# schematic.net
KiCad netlist of a schematic drawn in EAGLE
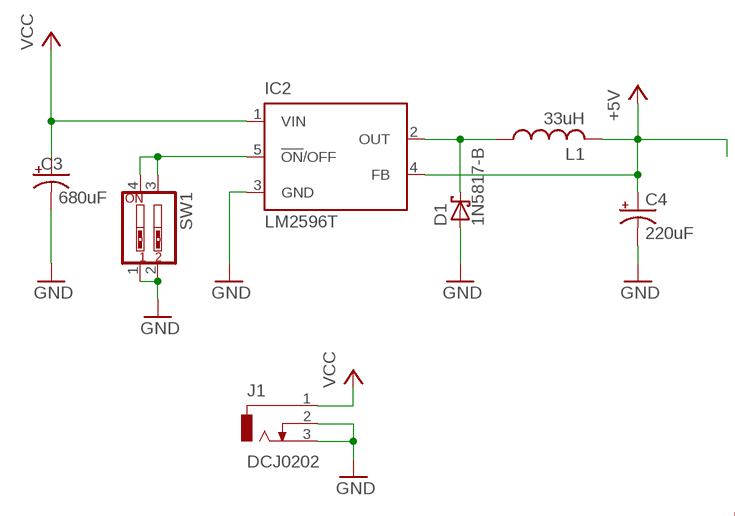
[diagram p0: schematic, sheet 1, part 1 of 2]
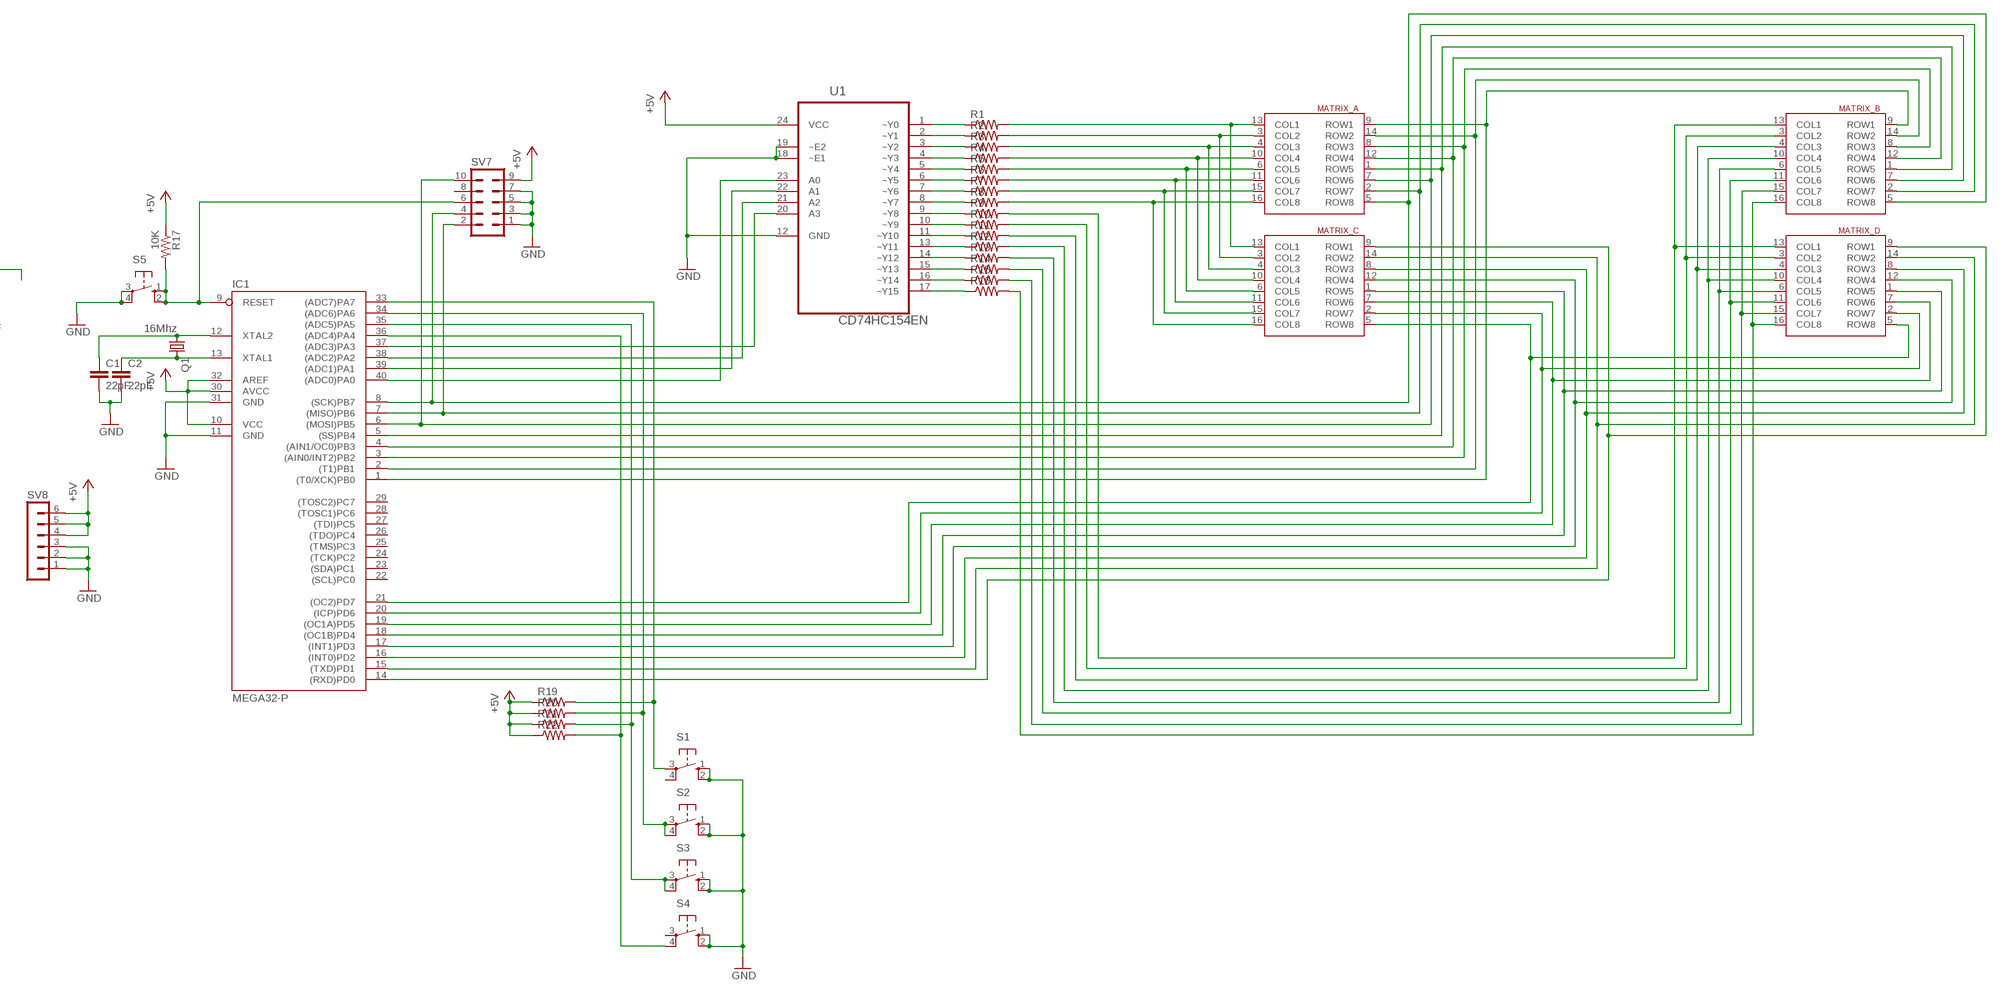
[diagram p1: schematic, sheet 1, part 2 of 2]

(export (version "E")
  (design (tool "Eeschema 10.0.6"))
  (components
    (comp (ref "C1")
      (value "22pF")
      (footprint "eagle-import:C025-024X044")
      (libsource (lib "eagle-import") (part "C-EU025-024X044"))
    )
    (comp (ref "C2")
      (value "22pF")
      (footprint "eagle-import:C025-024X044")
      (libsource (lib "eagle-import") (part "C-EU025-024X044"))
    )
    (comp (ref "C3")
      (value "680uF")
      (footprint "eagle-import:E3,5-8")
      (libsource (lib "eagle-import") (part "CPOL-USE3.5-8"))
    )
    (comp (ref "C4")
      (value "220uF")
      (footprint "eagle-import:E3,5-8")
      (libsource (lib "eagle-import") (part "CPOL-USE3.5-8"))
    )
    (comp (ref "D1")
      (value "1N5817-B")
      (footprint "eagle-import:DO41-7.6")
      (libsource (lib "eagle-import") (part "1N5817-B"))
    )
    (comp (ref "IC1")
      (value "MEGA32-P")
      (footprint "eagle-import:DIL40")
      (fields (field (name "MPN") "ATMEGA32-16PU"))
      (libsource (lib "eagle-import") (part "MEGA32-P"))
    )
    (comp (ref "IC2")
      (value "LM2596T")
      (footprint "eagle-import:T05D")
      (fields (field (name "MPN") "LM2596T-ADJ/LF02"))
      (libsource (lib "eagle-import") (part "LM2596T"))
    )
    (comp (ref "J1")
      (value "DCJ0202")
      (footprint "eagle-import:DCJ0202")
      (libsource (lib "eagle-import") (part "DCJ0202"))
    )
    (comp (ref "L1")
      (value "33uH")
      (footprint "eagle-import:0207_10")
      (libsource (lib "eagle-import") (part "L-US0207/10"))
    )
    (comp (ref "MATRIX_A")
      (value "LED_8X8_MATRIXYGD2/A")
      (footprint "eagle-import:MATRIX_8X8_38MM")
      (libsource (lib "eagle-import") (part "LED_8X8_MATRIXYGD2/A"))
    )
    (comp (ref "MATRIX_B")
      (value "LED_8X8_MATRIXYGD2/A")
      (footprint "eagle-import:MATRIX_8X8_38MM")
      (libsource (lib "eagle-import") (part "LED_8X8_MATRIXYGD2/A"))
    )
    (comp (ref "MATRIX_C")
      (value "LED_8X8_MATRIXYGD2/A")
      (footprint "eagle-import:MATRIX_8X8_38MM")
      (libsource (lib "eagle-import") (part "LED_8X8_MATRIXYGD2/A"))
    )
    (comp (ref "MATRIX_D")
      (value "LED_8X8_MATRIXYGD2/A")
      (footprint "eagle-import:MATRIX_8X8_38MM")
      (libsource (lib "eagle-import") (part "LED_8X8_MATRIXYGD2/A"))
    )
    (comp (ref "Q1")
      (value "16Mhz")
      (footprint "eagle-import:HC49_S")
      (libsource (lib "eagle-import") (part "CRYSTALHC49S"))
    )
    (comp (ref "R1")
      (value "R-US_0204/2V")
      (footprint "eagle-import:0204V")
      (libsource (lib "eagle-import") (part "R-US_0204/2V"))
    )
    (comp (ref "R2")
      (value "R-US_0204/2V")
      (footprint "eagle-import:0204V")
      (libsource (lib "eagle-import") (part "R-US_0204/2V"))
    )
    (comp (ref "R3")
      (value "R-US_0204/2V")
      (footprint "eagle-import:0204V")
      (libsource (lib "eagle-import") (part "R-US_0204/2V"))
    )
    (comp (ref "R4")
      (value "R-US_0204/2V")
      (footprint "eagle-import:0204V")
      (libsource (lib "eagle-import") (part "R-US_0204/2V"))
    )
    (comp (ref "R5")
      (value "R-US_0204/2V")
      (footprint "eagle-import:0204V")
      (libsource (lib "eagle-import") (part "R-US_0204/2V"))
    )
    (comp (ref "R6")
      (value "R-US_0204/2V")
      (footprint "eagle-import:0204V")
      (libsource (lib "eagle-import") (part "R-US_0204/2V"))
    )
    (comp (ref "R7")
      (value "R-US_0204/2V")
      (footprint "eagle-import:0204V")
      (libsource (lib "eagle-import") (part "R-US_0204/2V"))
    )
    (comp (ref "R8")
      (value "R-US_0204/2V")
      (footprint "eagle-import:0204V")
      (libsource (lib "eagle-import") (part "R-US_0204/2V"))
    )
    (comp (ref "R9")
      (value "R-US_0204/2V")
      (footprint "eagle-import:0204V")
      (libsource (lib "eagle-import") (part "R-US_0204/2V"))
    )
    (comp (ref "R10")
      (value "R-US_0204/2V")
      (footprint "eagle-import:0204V")
      (libsource (lib "eagle-import") (part "R-US_0204/2V"))
    )
    (comp (ref "R11")
      (value "R-US_0204/2V")
      (footprint "eagle-import:0204V")
      (libsource (lib "eagle-import") (part "R-US_0204/2V"))
    )
    (comp (ref "R12")
      (value "R-US_0204/2V")
      (footprint "eagle-import:0204V")
      (libsource (lib "eagle-import") (part "R-US_0204/2V"))
    )
    (comp (ref "R13")
      (value "R-US_0204/2V")
      (footprint "eagle-import:0204V")
      (libsource (lib "eagle-import") (part "R-US_0204/2V"))
    )
    (comp (ref "R14")
      (value "R-US_0204/2V")
      (footprint "eagle-import:0204V")
      (libsource (lib "eagle-import") (part "R-US_0204/2V"))
    )
    (comp (ref "R15")
      (value "R-US_0204/2V")
      (footprint "eagle-import:0204V")
      (libsource (lib "eagle-import") (part "R-US_0204/2V"))
    )
    (comp (ref "R16")
      (value "R-US_0204/2V")
      (footprint "eagle-import:0204V")
      (libsource (lib "eagle-import") (part "R-US_0204/2V"))
    )
    (comp (ref "R17")
      (value "10K")
      (footprint "eagle-import:0204_7")
      (libsource (lib "eagle-import") (part "resistor_348_R-US_0204/7"))
    )
    (comp (ref "R19")
      (value "R-US_0204/7")
      (footprint "eagle-import:0204_7")
      (libsource (lib "eagle-import") (part "R-US_0204/7"))
    )
    (comp (ref "R20")
      (value "R-US_0204/7")
      (footprint "eagle-import:0204_7")
      (libsource (lib "eagle-import") (part "R-US_0204/7"))
    )
    (comp (ref "R21")
      (value "R-US_0204/7")
      (footprint "eagle-import:0204_7")
      (libsource (lib "eagle-import") (part "R-US_0204/7"))
    )
    (comp (ref "R22")
      (value "R-US_0204/7")
      (footprint "eagle-import:0204_7")
      (libsource (lib "eagle-import") (part "R-US_0204/7"))
    )
    (comp (ref "S1")
      (value "10-XX")
      (footprint "eagle-import:B3F-10XX")
      (fields (field (name "MPN") "B3F-1000"))
      (libsource (lib "eagle-import") (part "10-XX"))
    )
    (comp (ref "S2")
      (value "10-XX")
      (footprint "eagle-import:B3F-10XX")
      (fields (field (name "MPN") "B3F-1000"))
      (libsource (lib "eagle-import") (part "10-XX"))
    )
    (comp (ref "S3")
      (value "10-XX")
      (footprint "eagle-import:B3F-10XX")
      (fields (field (name "MPN") "B3F-1000"))
      (libsource (lib "eagle-import") (part "10-XX"))
    )
    (comp (ref "S4")
      (value "10-XX")
      (footprint "eagle-import:B3F-10XX")
      (fields (field (name "MPN") "B3F-1000"))
      (libsource (lib "eagle-import") (part "10-XX"))
    )
    (comp (ref "S5")
      (value "10-XX")
      (footprint "eagle-import:B3F-10XX")
      (fields (field (name "MPN") "B3F-1000"))
      (libsource (lib "eagle-import") (part "10-XX"))
    )
    (comp (ref "SV7")
      (value "MA05-2")
      (footprint "eagle-import:MA05-2")
      (libsource (lib "eagle-import") (part "MA05-2"))
    )
    (comp (ref "SV8")
      (value "MA06-1")
      (footprint "eagle-import:MA06-1")
      (libsource (lib "eagle-import") (part "MA06-1"))
    )
    (comp (ref "SW1")
      (value "SW_DIP-2")
      (footprint "eagle-import:EDG-02")
      (libsource (lib "eagle-import") (part "SW_DIP-2"))
    )
    (comp (ref "U1")
      (value "CD74HC154EN")
      (footprint "eagle-import:DIP254P762X508-24")
      (libsource (lib "eagle-import") (part "CD74HC154EN"))
    )
  )
  (nets
    (net (code "1") (name "+5V") (class "Default")
      (node (ref "C4") (pin "+") (pinfunction "+_+") (pintype "passive"))
      (node (ref "IC1") (pin "10") (pinfunction "VCC_10") (pintype "power_in"))
      (node (ref "IC1") (pin "30") (pinfunction "AVCC_30") (pintype "power_in"))
      (node (ref "IC1") (pin "32") (pinfunction "AREF_32") (pintype "passive"))
      (node (ref "IC2") (pin "4") (pinfunction "FB_4") (pintype "input"))
      (node (ref "L1") (pin "2") (pinfunction "2_2") (pintype "passive"))
      (node (ref "R17") (pin "1") (pinfunction "1_1") (pintype "passive"))
      (node (ref "R19") (pin "1") (pinfunction "1_1") (pintype "passive"))
      (node (ref "R20") (pin "1") (pinfunction "1_1") (pintype "passive"))
      (node (ref "R21") (pin "1") (pinfunction "1_1") (pintype "passive"))
      (node (ref "R22") (pin "1") (pinfunction "1_1") (pintype "passive"))
      (node (ref "SV7") (pin "9") (pinfunction "9_9") (pintype "passive"))
      (node (ref "SV8") (pin "4") (pinfunction "4_4") (pintype "passive"))
      (node (ref "SV8") (pin "5") (pinfunction "5_5") (pintype "passive"))
      (node (ref "SV8") (pin "6") (pinfunction "6_6") (pintype "passive"))
      (node (ref "U1") (pin "24") (pinfunction "VCC_24") (pintype "power_in"))
    )
    (net (code "2") (name "GND") (class "Default")
      (node (ref "C1") (pin "2") (pinfunction "2_2") (pintype "passive"))
      (node (ref "C2") (pin "2") (pinfunction "2_2") (pintype "passive"))
      (node (ref "C3") (pin "-") (pinfunction "-_-") (pintype "passive"))
      (node (ref "C4") (pin "-") (pinfunction "-_-") (pintype "passive"))
      (node (ref "D1") (pin "A") (pinfunction "A_A") (pintype "passive"))
      (node (ref "IC1") (pin "11") (pinfunction "GND_11") (pintype "power_in"))
      (node (ref "IC1") (pin "31") (pinfunction "GND_31") (pintype "power_in"))
      (node (ref "IC2") (pin "3") (pinfunction "GND_3") (pintype "power_in"))
      (node (ref "J1") (pin "2") (pinfunction "2_2") (pintype "passive"))
      (node (ref "J1") (pin "3") (pinfunction "3_3") (pintype "passive"))
      (node (ref "S1") (pin "1") (pinfunction "S_1") (pintype "passive"))
      (node (ref "S1") (pin "2") (pinfunction "S1_2") (pintype "passive"))
      (node (ref "S2") (pin "1") (pinfunction "S_1") (pintype "passive"))
      (node (ref "S2") (pin "2") (pinfunction "S1_2") (pintype "passive"))
      (node (ref "S3") (pin "1") (pinfunction "S_1") (pintype "passive"))
      (node (ref "S3") (pin "2") (pinfunction "S1_2") (pintype "passive"))
      (node (ref "S4") (pin "1") (pinfunction "S_1") (pintype "passive"))
      (node (ref "S4") (pin "2") (pinfunction "S1_2") (pintype "passive"))
      (node (ref "S5") (pin "3") (pinfunction "P_3") (pintype "passive"))
      (node (ref "S5") (pin "4") (pinfunction "P1_4") (pintype "passive"))
      (node (ref "SV7") (pin "1") (pinfunction "1_1") (pintype "passive"))
      (node (ref "SV7") (pin "3") (pinfunction "3_3") (pintype "passive"))
      (node (ref "SV7") (pin "5") (pinfunction "5_5") (pintype "passive"))
      (node (ref "SV7") (pin "7") (pinfunction "7_7") (pintype "passive"))
      (node (ref "SV8") (pin "1") (pinfunction "1_1") (pintype "passive"))
      (node (ref "SV8") (pin "2") (pinfunction "2_2") (pintype "passive"))
      (node (ref "SV8") (pin "3") (pinfunction "3_3") (pintype "passive"))
      (node (ref "SW1") (pin "1") (pinfunction "1_1") (pintype "passive"))
      (node (ref "SW1") (pin "2") (pinfunction "2_2") (pintype "passive"))
      (node (ref "U1") (pin "12") (pinfunction "GND_12") (pintype "passive"))
      (node (ref "U1") (pin "18") (pinfunction "~{E1}_18") (pintype "input"))
      (node (ref "U1") (pin "19") (pinfunction "~{E2}_19") (pintype "input"))
    )
    (net (code "3") (name "Net-(IC1-(ADC0)PA0)") (class "Default")
      (node (ref "IC1") (pin "40") (pinfunction "(ADC0)PA0_40") (pintype "bidirectional"))
      (node (ref "U1") (pin "23") (pinfunction "A0_23") (pintype "input"))
    )
    (net (code "4") (name "Net-(IC1-(ADC1)PA1)") (class "Default")
      (node (ref "IC1") (pin "39") (pinfunction "(ADC1)PA1_39") (pintype "bidirectional"))
      (node (ref "U1") (pin "22") (pinfunction "A1_22") (pintype "input"))
    )
    (net (code "5") (name "Net-(IC1-(ADC2)PA2)") (class "Default")
      (node (ref "IC1") (pin "38") (pinfunction "(ADC2)PA2_38") (pintype "bidirectional"))
      (node (ref "U1") (pin "21") (pinfunction "A2_21") (pintype "input"))
    )
    (net (code "6") (name "Net-(IC1-(ADC3)PA3)") (class "Default")
      (node (ref "IC1") (pin "37") (pinfunction "(ADC3)PA3_37") (pintype "bidirectional"))
      (node (ref "U1") (pin "20") (pinfunction "A3_20") (pintype "input"))
    )
    (net (code "7") (name "Net-(IC1-(ADC4)PA4)") (class "Default")
      (node (ref "IC1") (pin "36") (pinfunction "(ADC4)PA4_36") (pintype "bidirectional"))
      (node (ref "R22") (pin "2") (pinfunction "2_2") (pintype "passive"))
      (node (ref "S4") (pin "4") (pinfunction "P1_4") (pintype "passive"))
    )
    (net (code "8") (name "Net-(IC1-(ADC5)PA5)") (class "Default")
      (node (ref "IC1") (pin "35") (pinfunction "(ADC5)PA5_35") (pintype "bidirectional"))
      (node (ref "R21") (pin "2") (pinfunction "2_2") (pintype "passive"))
      (node (ref "S3") (pin "3") (pinfunction "P_3") (pintype "passive"))
      (node (ref "S3") (pin "4") (pinfunction "P1_4") (pintype "passive"))
    )
    (net (code "9") (name "Net-(IC1-(ADC6)PA6)") (class "Default")
      (node (ref "IC1") (pin "34") (pinfunction "(ADC6)PA6_34") (pintype "bidirectional"))
      (node (ref "R20") (pin "2") (pinfunction "2_2") (pintype "passive"))
      (node (ref "S2") (pin "3") (pinfunction "P_3") (pintype "passive"))
      (node (ref "S2") (pin "4") (pinfunction "P1_4") (pintype "passive"))
    )
    (net (code "10") (name "Net-(IC1-(ADC7)PA7)") (class "Default")
      (node (ref "IC1") (pin "33") (pinfunction "(ADC7)PA7_33") (pintype "bidirectional"))
      (node (ref "R19") (pin "2") (pinfunction "2_2") (pintype "passive"))
      (node (ref "S1") (pin "3") (pinfunction "P_3") (pintype "passive"))
    )
    (net (code "11") (name "Net-(IC1-(AIN0{slash}INT2)PB2)") (class "Default")
      (node (ref "IC1") (pin "3") (pinfunction "(AIN0/INT2)PB2_3") (pintype "bidirectional"))
      (node (ref "MATRIX_A") (pin "8") (pinfunction "ROW3_8") (pintype "bidirectional"))
      (node (ref "MATRIX_B") (pin "8") (pinfunction "ROW3_8") (pintype "bidirectional"))
    )
    (net (code "12") (name "Net-(IC1-(AIN1{slash}OC0)PB3)") (class "Default")
      (node (ref "IC1") (pin "4") (pinfunction "(AIN1/OC0)PB3_4") (pintype "bidirectional"))
      (node (ref "MATRIX_A") (pin "12") (pinfunction "ROW4_12") (pintype "bidirectional"))
      (node (ref "MATRIX_B") (pin "12") (pinfunction "ROW4_12") (pintype "bidirectional"))
    )
    (net (code "13") (name "Net-(IC1-(ICP)PD6)") (class "Default")
      (node (ref "IC1") (pin "20") (pinfunction "(ICP)PD6_20") (pintype "bidirectional"))
      (node (ref "MATRIX_C") (pin "2") (pinfunction "ROW7_2") (pintype "bidirectional"))
      (node (ref "MATRIX_D") (pin "2") (pinfunction "ROW7_2") (pintype "bidirectional"))
    )
    (net (code "14") (name "Net-(IC1-(INT0)PD2)") (class "Default")
      (node (ref "IC1") (pin "16") (pinfunction "(INT0)PD2_16") (pintype "bidirectional"))
      (node (ref "MATRIX_C") (pin "8") (pinfunction "ROW3_8") (pintype "bidirectional"))
      (node (ref "MATRIX_D") (pin "8") (pinfunction "ROW3_8") (pintype "bidirectional"))
    )
    (net (code "15") (name "Net-(IC1-(INT1)PD3)") (class "Default")
      (node (ref "IC1") (pin "17") (pinfunction "(INT1)PD3_17") (pintype "bidirectional"))
      (node (ref "MATRIX_C") (pin "12") (pinfunction "ROW4_12") (pintype "bidirectional"))
      (node (ref "MATRIX_D") (pin "12") (pinfunction "ROW4_12") (pintype "bidirectional"))
    )
    (net (code "16") (name "Net-(IC1-(MISO)PB6)") (class "Default")
      (node (ref "IC1") (pin "7") (pinfunction "(MISO)PB6_7") (pintype "bidirectional"))
      (node (ref "MATRIX_A") (pin "2") (pinfunction "ROW7_2") (pintype "bidirectional"))
      (node (ref "MATRIX_B") (pin "2") (pinfunction "ROW7_2") (pintype "bidirectional"))
      (node (ref "SV7") (pin "2") (pinfunction "2_2") (pintype "passive"))
    )
    (net (code "17") (name "Net-(IC1-(MOSI)PB5)") (class "Default")
      (node (ref "IC1") (pin "6") (pinfunction "(MOSI)PB5_6") (pintype "bidirectional"))
      (node (ref "MATRIX_A") (pin "7") (pinfunction "ROW6_7") (pintype "bidirectional"))
      (node (ref "MATRIX_B") (pin "7") (pinfunction "ROW6_7") (pintype "bidirectional"))
      (node (ref "SV7") (pin "10") (pinfunction "10_10") (pintype "passive"))
    )
    (net (code "18") (name "Net-(IC1-(OC1A)PD5)") (class "Default")
      (node (ref "IC1") (pin "19") (pinfunction "(OC1A)PD5_19") (pintype "bidirectional"))
      (node (ref "MATRIX_C") (pin "7") (pinfunction "ROW6_7") (pintype "bidirectional"))
      (node (ref "MATRIX_D") (pin "7") (pinfunction "ROW6_7") (pintype "bidirectional"))
    )
    (net (code "19") (name "Net-(IC1-(OC1B)PD4)") (class "Default")
      (node (ref "IC1") (pin "18") (pinfunction "(OC1B)PD4_18") (pintype "bidirectional"))
      (node (ref "MATRIX_C") (pin "1") (pinfunction "ROW5_1") (pintype "bidirectional"))
      (node (ref "MATRIX_D") (pin "1") (pinfunction "ROW5_1") (pintype "bidirectional"))
    )
    (net (code "20") (name "Net-(IC1-(OC2)PD7)") (class "Default")
      (node (ref "IC1") (pin "21") (pinfunction "(OC2)PD7_21") (pintype "bidirectional"))
      (node (ref "MATRIX_C") (pin "5") (pinfunction "ROW8_5") (pintype "bidirectional"))
      (node (ref "MATRIX_D") (pin "5") (pinfunction "ROW8_5") (pintype "bidirectional"))
    )
    (net (code "21") (name "Net-(IC1-(RXD)PD0)") (class "Default")
      (node (ref "IC1") (pin "14") (pinfunction "(RXD)PD0_14") (pintype "bidirectional"))
      (node (ref "MATRIX_C") (pin "9") (pinfunction "ROW1_9") (pintype "bidirectional"))
      (node (ref "MATRIX_D") (pin "9") (pinfunction "ROW1_9") (pintype "bidirectional"))
    )
    (net (code "22") (name "Net-(IC1-(SCK)PB7)") (class "Default")
      (node (ref "IC1") (pin "8") (pinfunction "(SCK)PB7_8") (pintype "bidirectional"))
      (node (ref "MATRIX_A") (pin "5") (pinfunction "ROW8_5") (pintype "bidirectional"))
      (node (ref "MATRIX_B") (pin "5") (pinfunction "ROW8_5") (pintype "bidirectional"))
      (node (ref "SV7") (pin "4") (pinfunction "4_4") (pintype "passive"))
    )
    (net (code "23") (name "Net-(IC1-(SS)PB4)") (class "Default")
      (node (ref "IC1") (pin "5") (pinfunction "(SS)PB4_5") (pintype "bidirectional"))
      (node (ref "MATRIX_A") (pin "1") (pinfunction "ROW5_1") (pintype "bidirectional"))
      (node (ref "MATRIX_B") (pin "1") (pinfunction "ROW5_1") (pintype "bidirectional"))
    )
    (net (code "24") (name "Net-(IC1-(T0{slash}XCK)PB0)") (class "Default")
      (node (ref "IC1") (pin "1") (pinfunction "(T0/XCK)PB0_1") (pintype "bidirectional"))
      (node (ref "MATRIX_A") (pin "9") (pinfunction "ROW1_9") (pintype "bidirectional"))
      (node (ref "MATRIX_B") (pin "9") (pinfunction "ROW1_9") (pintype "bidirectional"))
    )
    (net (code "25") (name "Net-(IC1-(T1)PB1)") (class "Default")
      (node (ref "IC1") (pin "2") (pinfunction "(T1)PB1_2") (pintype "bidirectional"))
      (node (ref "MATRIX_A") (pin "14") (pinfunction "ROW2_14") (pintype "bidirectional"))
      (node (ref "MATRIX_B") (pin "14") (pinfunction "ROW2_14") (pintype "bidirectional"))
    )
    (net (code "26") (name "Net-(IC1-(TXD)PD1)") (class "Default")
      (node (ref "IC1") (pin "15") (pinfunction "(TXD)PD1_15") (pintype "bidirectional"))
      (node (ref "MATRIX_C") (pin "14") (pinfunction "ROW2_14") (pintype "bidirectional"))
      (node (ref "MATRIX_D") (pin "14") (pinfunction "ROW2_14") (pintype "bidirectional"))
    )
    (net (code "27") (name "Net-(IC1-RESET)") (class "Default")
      (node (ref "IC1") (pin "9") (pinfunction "RESET_9") (pintype "input"))
      (node (ref "R17") (pin "2") (pinfunction "2_2") (pintype "passive"))
      (node (ref "S5") (pin "1") (pinfunction "S_1") (pintype "passive"))
      (node (ref "S5") (pin "2") (pinfunction "S1_2") (pintype "passive"))
      (node (ref "SV7") (pin "6") (pinfunction "6_6") (pintype "passive"))
    )
    (net (code "28") (name "Net-(IC1-XTAL1)") (class "Default")
      (node (ref "C2") (pin "1") (pinfunction "1_1") (pintype "passive"))
      (node (ref "IC1") (pin "13") (pinfunction "XTAL1_13") (pintype "bidirectional"))
      (node (ref "Q1") (pin "2") (pinfunction "2_2") (pintype "passive"))
    )
    (net (code "29") (name "Net-(IC1-XTAL2)") (class "Default")
      (node (ref "C1") (pin "1") (pinfunction "1_1") (pintype "passive"))
      (node (ref "IC1") (pin "12") (pinfunction "XTAL2_12") (pintype "bidirectional"))
      (node (ref "Q1") (pin "1") (pinfunction "1_1") (pintype "passive"))
    )
    (net (code "30") (name "Net-(IC2-OUT)") (class "Default")
      (node (ref "D1") (pin "C") (pinfunction "C_C") (pintype "passive"))
      (node (ref "IC2") (pin "2") (pinfunction "OUT_2") (pintype "output"))
      (node (ref "L1") (pin "1") (pinfunction "1_1") (pintype "passive"))
    )
    (net (code "31") (name "Net-(IC2-~{ON}{slash}OFF)") (class "Default")
      (node (ref "IC2") (pin "5") (pinfunction "~{ON}/OFF_5") (pintype "input"))
      (node (ref "SW1") (pin "3") (pinfunction "3_3") (pintype "passive"))
      (node (ref "SW1") (pin "4") (pinfunction "4_4") (pintype "passive"))
    )
    (net (code "32") (name "Net-(MATRIX_A-COL1)") (class "Default")
      (node (ref "MATRIX_A") (pin "13") (pinfunction "COL1_13") (pintype "bidirectional"))
      (node (ref "MATRIX_C") (pin "13") (pinfunction "COL1_13") (pintype "bidirectional"))
      (node (ref "R1") (pin "2") (pinfunction "2_2") (pintype "passive"))
    )
    (net (code "33") (name "Net-(MATRIX_A-COL2)") (class "Default")
      (node (ref "MATRIX_A") (pin "3") (pinfunction "COL2_3") (pintype "bidirectional"))
      (node (ref "MATRIX_C") (pin "3") (pinfunction "COL2_3") (pintype "bidirectional"))
      (node (ref "R2") (pin "2") (pinfunction "2_2") (pintype "passive"))
    )
    (net (code "34") (name "Net-(MATRIX_A-COL3)") (class "Default")
      (node (ref "MATRIX_A") (pin "4") (pinfunction "COL3_4") (pintype "bidirectional"))
      (node (ref "MATRIX_C") (pin "4") (pinfunction "COL3_4") (pintype "bidirectional"))
      (node (ref "R3") (pin "2") (pinfunction "2_2") (pintype "passive"))
    )
    (net (code "35") (name "Net-(MATRIX_A-COL4)") (class "Default")
      (node (ref "MATRIX_A") (pin "10") (pinfunction "COL4_10") (pintype "bidirectional"))
      (node (ref "MATRIX_C") (pin "10") (pinfunction "COL4_10") (pintype "bidirectional"))
      (node (ref "R4") (pin "2") (pinfunction "2_2") (pintype "passive"))
    )
    (net (code "36") (name "Net-(MATRIX_A-COL5)") (class "Default")
      (node (ref "MATRIX_A") (pin "6") (pinfunction "COL5_6") (pintype "bidirectional"))
      (node (ref "MATRIX_C") (pin "6") (pinfunction "COL5_6") (pintype "bidirectional"))
      (node (ref "R5") (pin "2") (pinfunction "2_2") (pintype "passive"))
    )
    (net (code "37") (name "Net-(MATRIX_A-COL6)") (class "Default")
      (node (ref "MATRIX_A") (pin "11") (pinfunction "COL6_11") (pintype "bidirectional"))
      (node (ref "MATRIX_C") (pin "11") (pinfunction "COL6_11") (pintype "bidirectional"))
      (node (ref "R6") (pin "2") (pinfunction "2_2") (pintype "passive"))
    )
    (net (code "38") (name "Net-(MATRIX_A-COL7)") (class "Default")
      (node (ref "MATRIX_A") (pin "15") (pinfunction "COL7_15") (pintype "bidirectional"))
      (node (ref "MATRIX_C") (pin "15") (pinfunction "COL7_15") (pintype "bidirectional"))
      (node (ref "R7") (pin "2") (pinfunction "2_2") (pintype "passive"))
    )
    (net (code "39") (name "Net-(MATRIX_A-COL8)") (class "Default")
      (node (ref "MATRIX_A") (pin "16") (pinfunction "COL8_16") (pintype "bidirectional"))
      (node (ref "MATRIX_C") (pin "16") (pinfunction "COL8_16") (pintype "bidirectional"))
      (node (ref "R8") (pin "2") (pinfunction "2_2") (pintype "passive"))
    )
    (net (code "40") (name "Net-(MATRIX_B-COL1)") (class "Default")
      (node (ref "MATRIX_B") (pin "13") (pinfunction "COL1_13") (pintype "bidirectional"))
      (node (ref "MATRIX_D") (pin "13") (pinfunction "COL1_13") (pintype "bidirectional"))
      (node (ref "R9") (pin "2") (pinfunction "2_2") (pintype "passive"))
    )
    (net (code "41") (name "Net-(MATRIX_B-COL2)") (class "Default")
      (node (ref "MATRIX_B") (pin "3") (pinfunction "COL2_3") (pintype "bidirectional"))
      (node (ref "MATRIX_D") (pin "3") (pinfunction "COL2_3") (pintype "bidirectional"))
      (node (ref "R10") (pin "2") (pinfunction "2_2") (pintype "passive"))
    )
    (net (code "42") (name "Net-(MATRIX_B-COL3)") (class "Default")
      (node (ref "MATRIX_B") (pin "4") (pinfunction "COL3_4") (pintype "bidirectional"))
      (node (ref "MATRIX_D") (pin "4") (pinfunction "COL3_4") (pintype "bidirectional"))
      (node (ref "R11") (pin "2") (pinfunction "2_2") (pintype "passive"))
    )
    (net (code "43") (name "Net-(MATRIX_B-COL4)") (class "Default")
      (node (ref "MATRIX_B") (pin "10") (pinfunction "COL4_10") (pintype "bidirectional"))
      (node (ref "MATRIX_D") (pin "10") (pinfunction "COL4_10") (pintype "bidirectional"))
      (node (ref "R12") (pin "2") (pinfunction "2_2") (pintype "passive"))
    )
    (net (code "44") (name "Net-(MATRIX_B-COL5)") (class "Default")
      (node (ref "MATRIX_B") (pin "6") (pinfunction "COL5_6") (pintype "bidirectional"))
      (node (ref "MATRIX_D") (pin "6") (pinfunction "COL5_6") (pintype "bidirectional"))
      (node (ref "R13") (pin "2") (pinfunction "2_2") (pintype "passive"))
    )
    (net (code "45") (name "Net-(MATRIX_B-COL6)") (class "Default")
      (node (ref "MATRIX_B") (pin "11") (pinfunction "COL6_11") (pintype "bidirectional"))
      (node (ref "MATRIX_D") (pin "11") (pinfunction "COL6_11") (pintype "bidirectional"))
      (node (ref "R14") (pin "2") (pinfunction "2_2") (pintype "passive"))
    )
    (net (code "46") (name "Net-(MATRIX_B-COL7)") (class "Default")
      (node (ref "MATRIX_B") (pin "15") (pinfunction "COL7_15") (pintype "bidirectional"))
      (node (ref "MATRIX_D") (pin "15") (pinfunction "COL7_15") (pintype "bidirectional"))
      (node (ref "R15") (pin "2") (pinfunction "2_2") (pintype "passive"))
    )
    (net (code "47") (name "Net-(MATRIX_B-COL8)") (class "Default")
      (node (ref "MATRIX_B") (pin "16") (pinfunction "COL8_16") (pintype "bidirectional"))
      (node (ref "MATRIX_D") (pin "16") (pinfunction "COL8_16") (pintype "bidirectional"))
      (node (ref "R16") (pin "2") (pinfunction "2_2") (pintype "passive"))
    )
    (net (code "48") (name "Net-(U1-~{Y0})") (class "Default")
      (node (ref "R1") (pin "1") (pinfunction "1_1") (pintype "passive"))
      (node (ref "U1") (pin "1") (pinfunction "~{Y0}_1") (pintype "output"))
    )
    (net (code "49") (name "Net-(U1-~{Y1})") (class "Default")
      (node (ref "R2") (pin "1") (pinfunction "1_1") (pintype "passive"))
      (node (ref "U1") (pin "2") (pinfunction "~{Y1}_2") (pintype "output"))
    )
    (net (code "50") (name "Net-(U1-~{Y2})") (class "Default")
      (node (ref "R3") (pin "1") (pinfunction "1_1") (pintype "passive"))
      (node (ref "U1") (pin "3") (pinfunction "~{Y2}_3") (pintype "output"))
    )
    (net (code "51") (name "Net-(U1-~{Y3})") (class "Default")
      (node (ref "R4") (pin "1") (pinfunction "1_1") (pintype "passive"))
      (node (ref "U1") (pin "4") (pinfunction "~{Y3}_4") (pintype "output"))
    )
    (net (code "52") (name "Net-(U1-~{Y4})") (class "Default")
      (node (ref "R5") (pin "1") (pinfunction "1_1") (pintype "passive"))
      (node (ref "U1") (pin "5") (pinfunction "~{Y4}_5") (pintype "output"))
    )
    (net (code "53") (name "Net-(U1-~{Y5})") (class "Default")
      (node (ref "R6") (pin "1") (pinfunction "1_1") (pintype "passive"))
      (node (ref "U1") (pin "6") (pinfunction "~{Y5}_6") (pintype "output"))
    )
    (net (code "54") (name "Net-(U1-~{Y6})") (class "Default")
      (node (ref "R7") (pin "1") (pinfunction "1_1") (pintype "passive"))
      (node (ref "U1") (pin "7") (pinfunction "~{Y6}_7") (pintype "output"))
    )
    (net (code "55") (name "Net-(U1-~{Y7})") (class "Default")
      (node (ref "R8") (pin "1") (pinfunction "1_1") (pintype "passive"))
      (node (ref "U1") (pin "8") (pinfunction "~{Y7}_8") (pintype "output"))
    )
    (net (code "56") (name "Net-(U1-~{Y8})") (class "Default")
      (node (ref "R9") (pin "1") (pinfunction "1_1") (pintype "passive"))
      (node (ref "U1") (pin "9") (pinfunction "~{Y8}_9") (pintype "output"))
    )
    (net (code "57") (name "Net-(U1-~{Y9})") (class "Default")
      (node (ref "R10") (pin "1") (pinfunction "1_1") (pintype "passive"))
      (node (ref "U1") (pin "10") (pinfunction "~{Y9}_10") (pintype "output"))
    )
    (net (code "58") (name "Net-(U1-~{Y10})") (class "Default")
      (node (ref "R11") (pin "1") (pinfunction "1_1") (pintype "passive"))
      (node (ref "U1") (pin "11") (pinfunction "~{Y10}_11") (pintype "output"))
    )
    (net (code "59") (name "Net-(U1-~{Y11})") (class "Default")
      (node (ref "R12") (pin "1") (pinfunction "1_1") (pintype "passive"))
      (node (ref "U1") (pin "13") (pinfunction "~{Y11}_13") (pintype "output"))
    )
    (net (code "60") (name "Net-(U1-~{Y12})") (class "Default")
      (node (ref "R13") (pin "1") (pinfunction "1_1") (pintype "passive"))
      (node (ref "U1") (pin "14") (pinfunction "~{Y12}_14") (pintype "output"))
    )
    (net (code "61") (name "Net-(U1-~{Y13})") (class "Default")
      (node (ref "R14") (pin "1") (pinfunction "1_1") (pintype "passive"))
      (node (ref "U1") (pin "15") (pinfunction "~{Y13}_15") (pintype "output"))
    )
    (net (code "62") (name "Net-(U1-~{Y14})") (class "Default")
      (node (ref "R15") (pin "1") (pinfunction "1_1") (pintype "passive"))
      (node (ref "U1") (pin "16") (pinfunction "~{Y14}_16") (pintype "output"))
    )
    (net (code "63") (name "Net-(U1-~{Y15})") (class "Default")
      (node (ref "R16") (pin "1") (pinfunction "1_1") (pintype "passive"))
      (node (ref "U1") (pin "17") (pinfunction "~{Y15}_17") (pintype "output"))
    )
    (net (code "64") (name "VCC") (class "Default")
      (node (ref "C3") (pin "+") (pinfunction "+_+") (pintype "passive"))
      (node (ref "IC2") (pin "1") (pinfunction "VIN_1") (pintype "input"))
      (node (ref "J1") (pin "1") (pinfunction "1_1") (pintype "passive"))
    )
    (net (code "65") (name "unconnected-(IC1-(SCL)PC0-Pad22)") (class "Default")
      (node (ref "IC1") (pin "22") (pinfunction "(SCL)PC0_22") (pintype "bidirectional"))
    )
    (net (code "66") (name "unconnected-(IC1-(SDA)PC1-Pad23)") (class "Default")
      (node (ref "IC1") (pin "23") (pinfunction "(SDA)PC1_23") (pintype "bidirectional"))
    )
    (net (code "67") (name "unconnected-(IC1-(TCK)PC2-Pad24)") (class "Default")
      (node (ref "IC1") (pin "24") (pinfunction "(TCK)PC2_24") (pintype "bidirectional"))
    )
    (net (code "68") (name "unconnected-(IC1-(TDI)PC5-Pad27)") (class "Default")
      (node (ref "IC1") (pin "27") (pinfunction "(TDI)PC5_27") (pintype "bidirectional"))
    )
    (net (code "69") (name "unconnected-(IC1-(TDO)PC4-Pad26)") (class "Default")
      (node (ref "IC1") (pin "26") (pinfunction "(TDO)PC4_26") (pintype "bidirectional"))
    )
    (net (code "70") (name "unconnected-(IC1-(TMS)PC3-Pad25)") (class "Default")
      (node (ref "IC1") (pin "25") (pinfunction "(TMS)PC3_25") (pintype "bidirectional"))
    )
    (net (code "71") (name "unconnected-(IC1-(TOSC1)PC6-Pad28)") (class "Default")
      (node (ref "IC1") (pin "28") (pinfunction "(TOSC1)PC6_28") (pintype "bidirectional"))
    )
    (net (code "72") (name "unconnected-(IC1-(TOSC2)PC7-Pad29)") (class "Default")
      (node (ref "IC1") (pin "29") (pinfunction "(TOSC2)PC7_29") (pintype "bidirectional"))
    )
    (net (code "73") (name "unconnected-(S1-P1-Pad4)") (class "Default")
      (node (ref "S1") (pin "4") (pinfunction "P1_4") (pintype "passive"))
    )
    (net (code "74") (name "unconnected-(S4-P-Pad3)") (class "Default")
      (node (ref "S4") (pin "3") (pinfunction "P_3") (pintype "passive"))
    )
    (net (code "75") (name "unconnected-(SV7-Pad8)") (class "Default")
      (node (ref "SV7") (pin "8") (pinfunction "8_8") (pintype "passive"))
    )
  )
)
